# INT_REG.net
KiCad netlist of a schematic drawn in Altium Designer
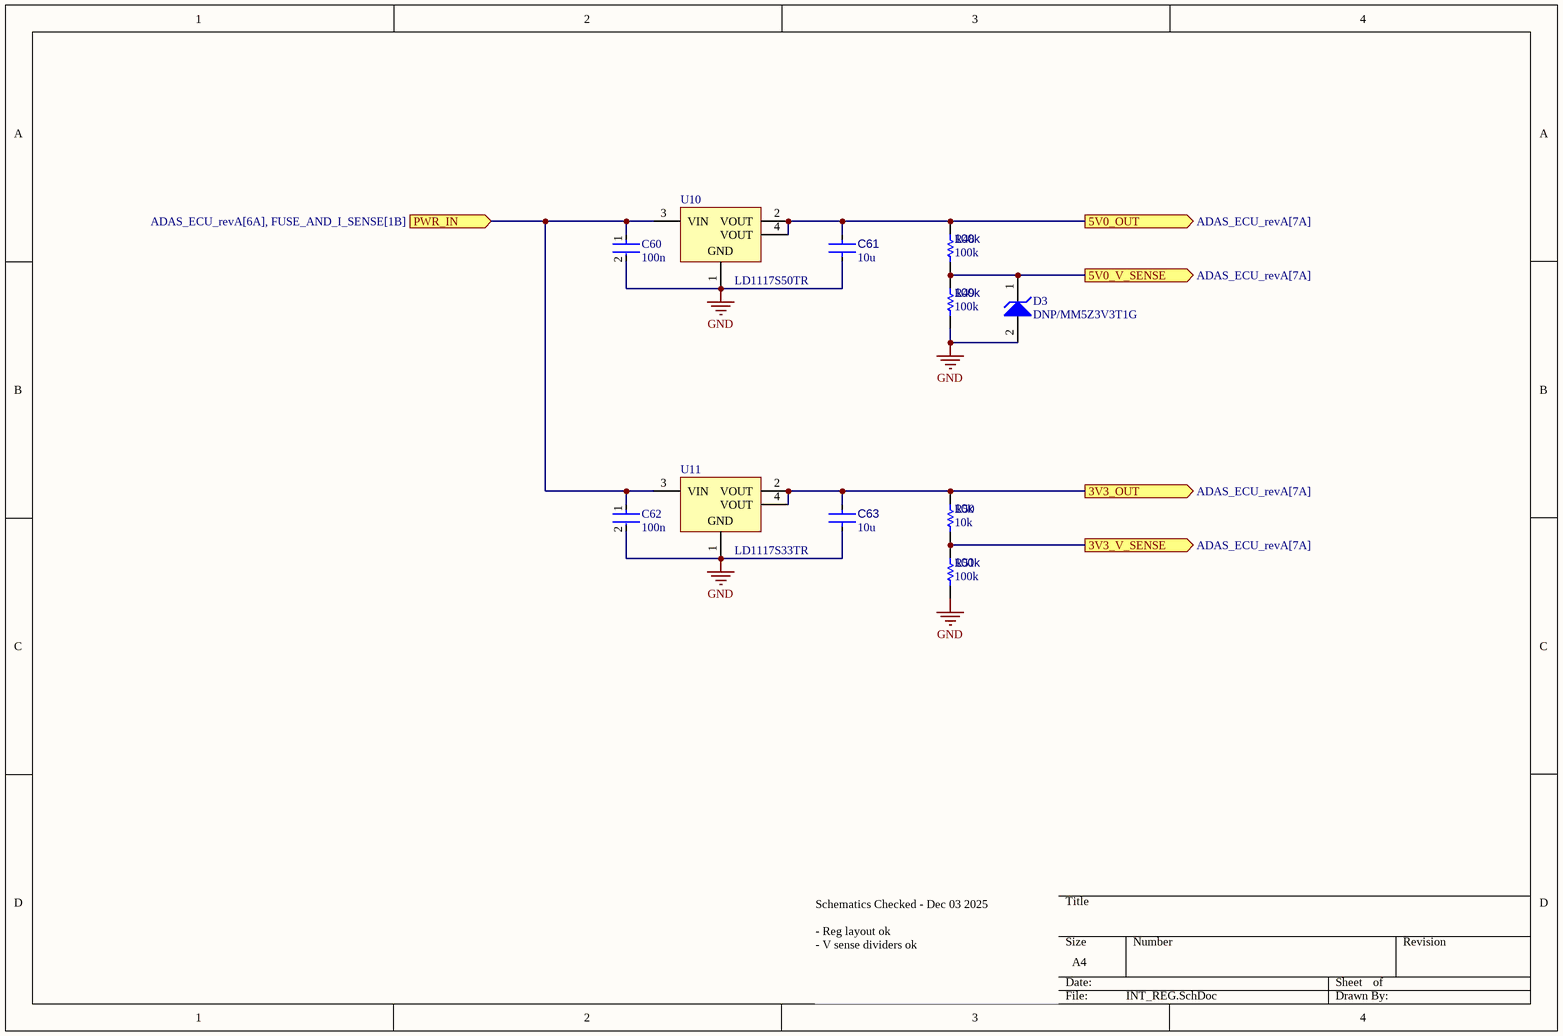
[diagram p0: INT_REG.SchDoc]

(export (version "E")
  (design (tool "Eeschema 10.0.6"))
  (components
    (comp (ref "C60")
      (value "100n")
      (footprint "FP-0402-L_1_0_0_05-W_0_5-IPC_A")
      (description "LARGE PADS, 0402 CAP, CHANGE COMMENT TO MATCH REAL P/N")
      (libsource (lib "Space Concordia") (part "b4654b650e69147ec39a6b967a45e02"))
    )
    (comp (ref "C61")
      (value "10u")
      (footprint "C0805A")
      (description "Non-polarized capacitor")
      (libsource (lib "Space Concordia") (part "Capacitor"))
    )
    (comp (ref "C62")
      (value "100n")
      (footprint "FP-0402-L_1_0_0_05-W_0_5-IPC_A")
      (description "LARGE PADS, 0402 CAP, CHANGE COMMENT TO MATCH REAL P/N")
      (libsource (lib "Space Concordia") (part "b4654b650e69147ec39a6b967a45e02"))
    )
    (comp (ref "C63")
      (value "10u")
      (footprint "C0805A")
      (description "Non-polarized capacitor")
      (libsource (lib "Space Concordia") (part "Capacitor"))
    )
    (comp (ref "D3")
      (value "DNP/MM5Z3V3T1G")
      (footprint "ONSC-SOD-523-2-502-01_V")
      (description "Zener Voltage Regulator, 500 mW, 2-Pin SOD-523, Pb-Free, Tape and Reel")
      (fields (field (name "MANUFACTURER") "On Semiconductor") (field (name "PARTNUMBER") "MM5Z3V3T1G"))
      (libsource (lib "Altium Content Vault") (part "ONSC-K1A2-2"))
    )
    (comp (ref "R48")
      (value "100k")
      (footprint "R0603B")
      (description "Resistor")
      (fields (field (name "ALTIUM_VALUE") "100k"))
      (libsource (lib "Space Concordia") (part "Resistor"))
    )
    (comp (ref "R49")
      (value "100k")
      (footprint "R0603B")
      (description "Resistor")
      (fields (field (name "ALTIUM_VALUE") "100k"))
      (libsource (lib "Space Concordia") (part "Resistor"))
    )
    (comp (ref "R50")
      (value "10k")
      (footprint "R0603B")
      (description "Resistor")
      (fields (field (name "ALTIUM_VALUE") "10k"))
      (libsource (lib "Space Concordia") (part "Resistor"))
    )
    (comp (ref "R51")
      (value "100k")
      (footprint "R0603B")
      (description "Resistor")
      (fields (field (name "ALTIUM_VALUE") "100k"))
      (libsource (lib "Space Concordia") (part "Resistor"))
    )
    (comp (ref "U10")
      (value "LD1117S50TR")
      (footprint "SOT-223_L")
      (description "Fixed Low Drop Positive Voltage Regulator, 5V, 4-Pin SOT-223, Tape and Reel")
      (libsource (lib "Altium Content Vault") (part "PM-REG-LD1117-SOT4"))
    )
    (comp (ref "U11")
      (value "LD1117S33TR")
      (footprint "SOT-223_L")
      (description "Fixed Low Drop Positive Voltage Regulator, 3.3V, 4-Pin SOT-223, Tape and Reel")
      (libsource (lib "Altium Content Vault") (part "PM-REG-LD1117-SOT4"))
    )
  )
  (nets
    (net (code "1") (name "/3V3_OUT") (class "Default")
      (node (ref "C63") (pin "1") (pinfunction "1_1") (pintype "passive"))
      (node (ref "R50") (pin "1") (pinfunction "1_1") (pintype "passive"))
      (node (ref "U11") (pin "2") (pinfunction "VOUT_2") (pintype "power_in"))
      (node (ref "U11") (pin "4") (pinfunction "VOUT_4") (pintype "power_in"))
    )
    (net (code "2") (name "/3V3_V_SENSE") (class "Default")
      (node (ref "R50") (pin "2") (pinfunction "2_2") (pintype "passive"))
      (node (ref "R51") (pin "1") (pinfunction "1_1") (pintype "passive"))
    )
    (net (code "3") (name "/5V0_OUT") (class "Default")
      (node (ref "C61") (pin "1") (pinfunction "1_1") (pintype "passive"))
      (node (ref "R48") (pin "1") (pinfunction "1_1") (pintype "passive"))
      (node (ref "U10") (pin "2") (pinfunction "VOUT_2") (pintype "power_in"))
      (node (ref "U10") (pin "4") (pinfunction "VOUT_4") (pintype "power_in"))
    )
    (net (code "4") (name "/5V0_V_SENSE") (class "Default")
      (node (ref "D3") (pin "1") (pinfunction "K_1") (pintype "passive"))
      (node (ref "R48") (pin "2") (pinfunction "2_2") (pintype "passive"))
      (node (ref "R49") (pin "1") (pinfunction "1_1") (pintype "passive"))
    )
    (net (code "5") (name "/PWR_IN") (class "Default")
      (node (ref "C60") (pin "1") (pinfunction "1_1") (pintype "passive"))
      (node (ref "C62") (pin "1") (pinfunction "1_1") (pintype "passive"))
      (node (ref "U10") (pin "3") (pinfunction "VIN_3") (pintype "power_in"))
      (node (ref "U11") (pin "3") (pinfunction "VIN_3") (pintype "power_in"))
    )
    (net (code "6") (name "GND") (class "Default")
      (node (ref "C60") (pin "2") (pinfunction "2_2") (pintype "passive"))
      (node (ref "C61") (pin "2") (pinfunction "2_2") (pintype "passive"))
      (node (ref "C62") (pin "2") (pinfunction "2_2") (pintype "passive"))
      (node (ref "C63") (pin "2") (pinfunction "2_2") (pintype "passive"))
      (node (ref "D3") (pin "2") (pinfunction "A_2") (pintype "passive"))
      (node (ref "R49") (pin "2") (pinfunction "2_2") (pintype "passive"))
      (node (ref "R51") (pin "2") (pinfunction "2_2") (pintype "passive"))
      (node (ref "U10") (pin "1") (pinfunction "GND_1") (pintype "power_in"))
      (node (ref "U11") (pin "1") (pinfunction "GND_1") (pintype "power_in"))
    )
  )
)
